# Main.net
KiCad netlist of a schematic drawn in EAGLE
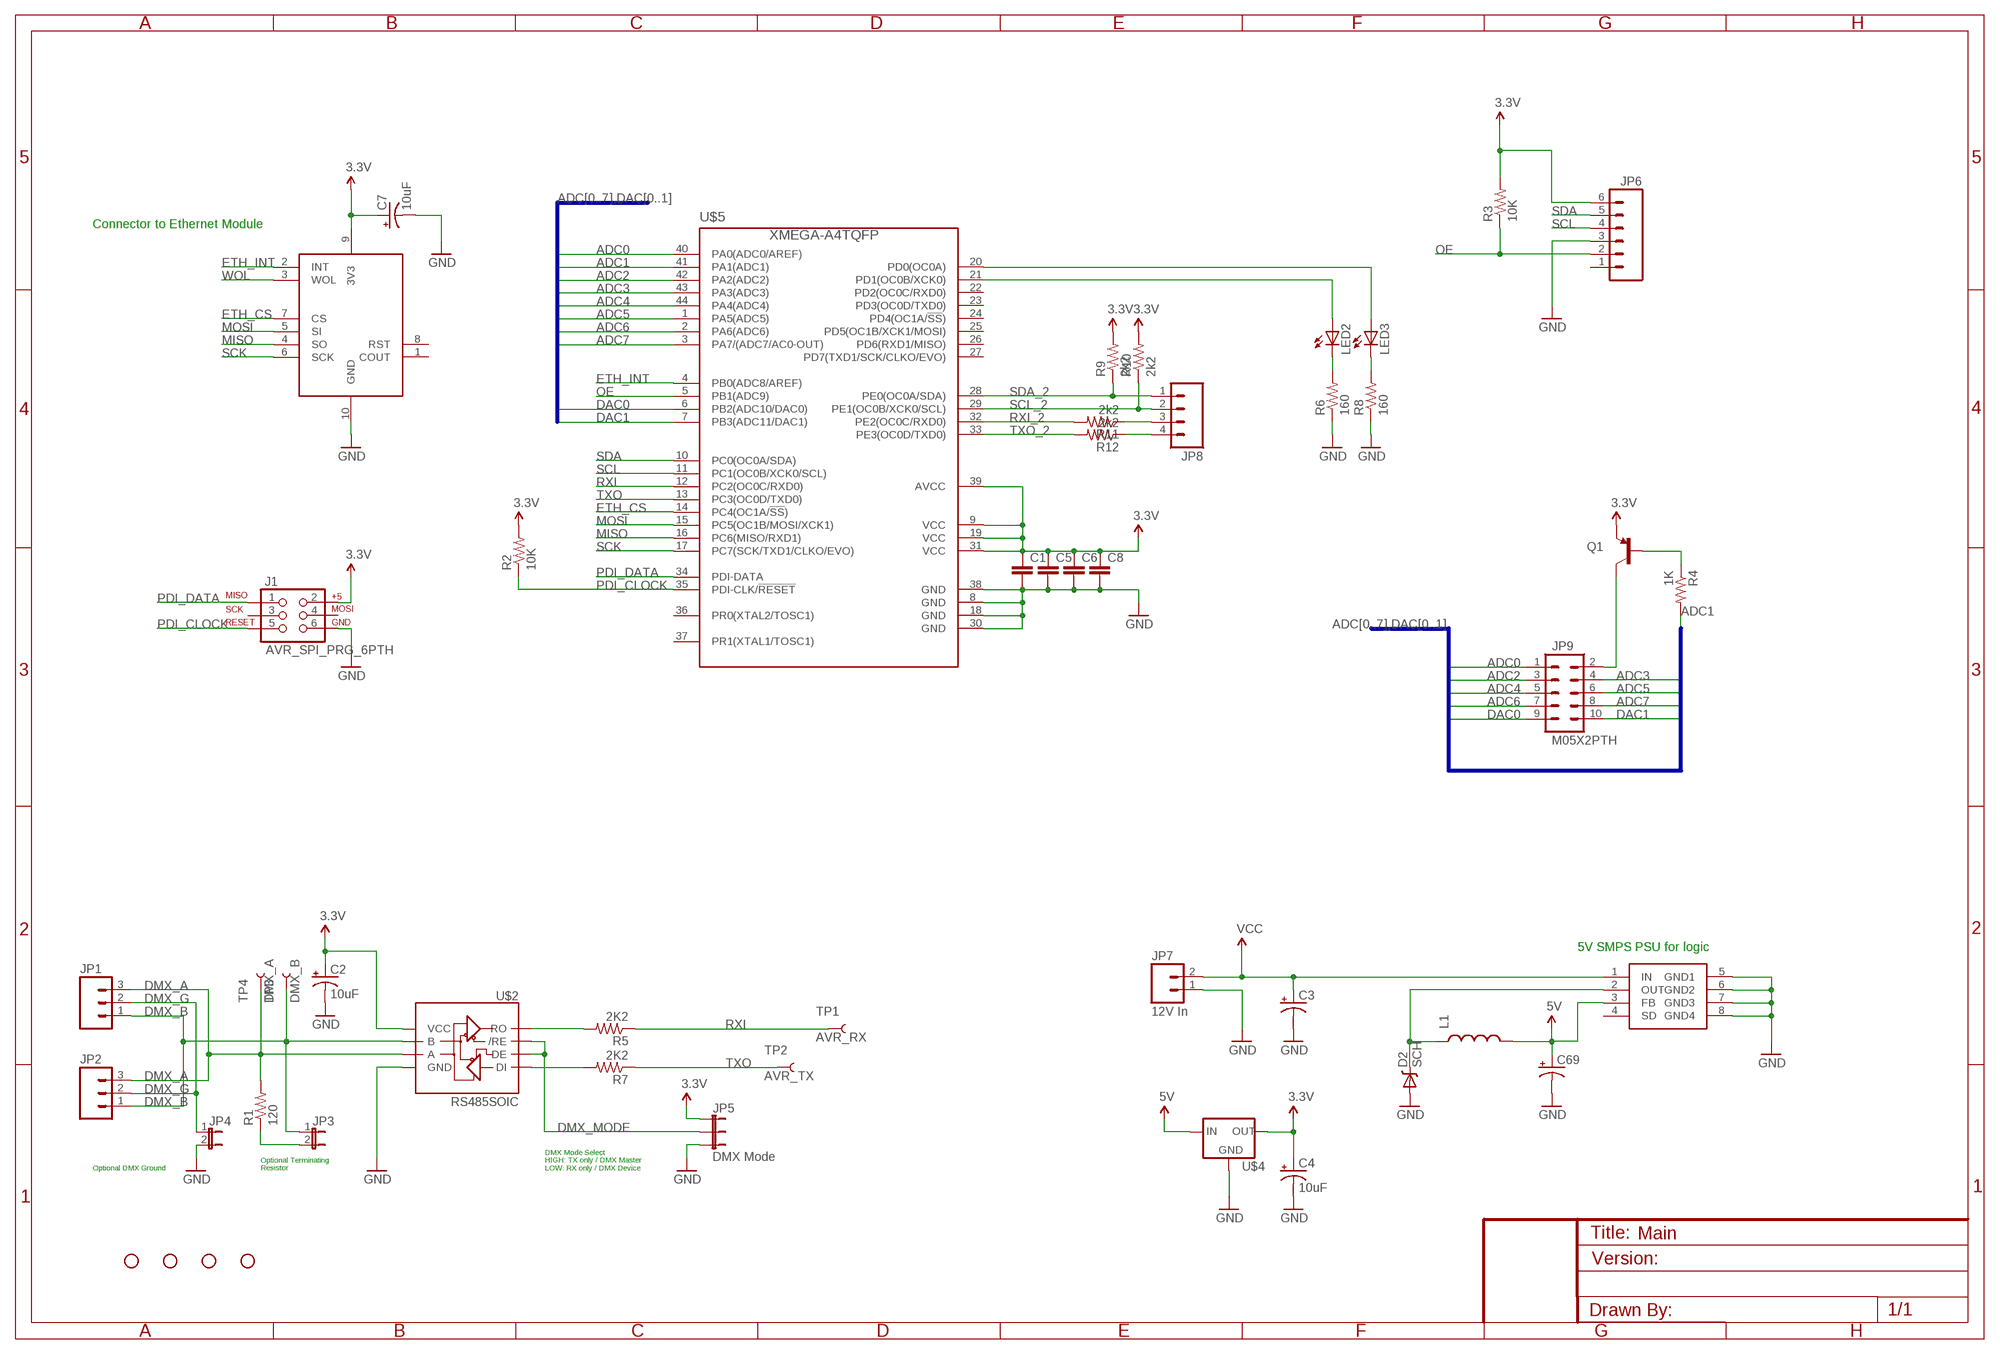
[diagram p0: schematic, sheet 1]

(export (version "E")
  (design (tool "Eeschema 10.0.6"))
  (components
    (comp (ref "C1")
      (value "CAP0603-CAP")
      (footprint "eagle-import:0603-CAP")
      (libsource (lib "eagle-import") (part "CAP0603-CAP"))
    )
    (comp (ref "C2")
      (value "10uF")
      (footprint "eagle-import:EIA3216")
      (libsource (lib "eagle-import") (part "CAP_POL1206"))
    )
    (comp (ref "C3")
      (value "CAP_POLPTH1")
      (footprint "eagle-import:CPOL-RADIAL-100UF-25V")
      (libsource (lib "eagle-import") (part "CAP_POLPTH1"))
    )
    (comp (ref "C4")
      (value "10uF")
      (footprint "eagle-import:EIA3216")
      (libsource (lib "eagle-import") (part "CAP_POL1206"))
    )
    (comp (ref "C5")
      (value "CAP0603-CAP")
      (footprint "eagle-import:0603-CAP")
      (libsource (lib "eagle-import") (part "CAP0603-CAP"))
    )
    (comp (ref "C6")
      (value "CAP0603-CAP")
      (footprint "eagle-import:0603-CAP")
      (libsource (lib "eagle-import") (part "CAP0603-CAP"))
    )
    (comp (ref "C7")
      (value "10uF")
      (footprint "eagle-import:EIA3216")
      (libsource (lib "eagle-import") (part "CAP_POL1206"))
    )
    (comp (ref "C8")
      (value "CAP0603-CAP")
      (footprint "eagle-import:0603-CAP")
      (libsource (lib "eagle-import") (part "CAP0603-CAP"))
    )
    (comp (ref "C69")
      (value "CAP_POLPTH1")
      (footprint "eagle-import:CPOL-RADIAL-100UF-25V")
      (libsource (lib "eagle-import") (part "CAP_POLPTH1"))
    )
    (comp (ref "D2")
      (value "SCH")
      (footprint "eagle-import:SMA-DIODE")
      (libsource (lib "eagle-import") (part "DIODE-SCHOTTKY_"))
    )
    (comp (ref "J1")
      (value "AVR_SPI_PRG_6PTH")
      (footprint "eagle-import:2X3")
      (libsource (lib "eagle-import") (part "AVR_SPI_PRG_6PTH"))
    )
    (comp (ref "JP1")
      (value "M03POLAR")
      (footprint "eagle-import:MOLEX-1X3")
      (libsource (lib "eagle-import") (part "M03POLAR"))
    )
    (comp (ref "JP2")
      (value "M03POLAR")
      (footprint "eagle-import:MOLEX-1X3")
      (libsource (lib "eagle-import") (part "M03POLAR"))
    )
    (comp (ref "JP3")
      (value "JUMPER-2PTH")
      (footprint "eagle-import:1X02")
      (libsource (lib "eagle-import") (part "JUMPER-2PTH"))
    )
    (comp (ref "JP4")
      (value "JUMPER-2PTH")
      (footprint "eagle-import:1X02")
      (libsource (lib "eagle-import") (part "JUMPER-2PTH"))
    )
    (comp (ref "JP5")
      (value "DMX Mode")
      (footprint "eagle-import:1X03")
      (libsource (lib "eagle-import") (part "JUMPER-3PTH"))
    )
    (comp (ref "JP6")
      (value "M06POLAR")
      (footprint "eagle-import:MOLEX-1X6")
      (libsource (lib "eagle-import") (part "M06POLAR"))
    )
    (comp (ref "JP7")
      (value "12V In")
      (footprint "eagle-import:SCREWTERMINAL-3.5MM-2")
      (libsource (lib "eagle-import") (part "M023.5MM"))
    )
    (comp (ref "JP8")
      (value "M04PTH")
      (footprint "eagle-import:1X04")
      (libsource (lib "eagle-import") (part "M04PTH"))
    )
    (comp (ref "JP9")
      (value "M05X2PTH")
      (footprint "eagle-import:AVR_ICSP")
      (libsource (lib "eagle-import") (part "M05X2PTH"))
    )
    (comp (ref "L1")
      (value "INDUCTOR1206H*")
      (footprint "eagle-import:INDUCTOR-1206")
      (libsource (lib "eagle-import") (part "INDUCTORH1206"))
    )
    (comp (ref "LED2")
      (value "LED5MM")
      (footprint "eagle-import:LED5MM")
      (libsource (lib "eagle-import") (part "LED5MM"))
    )
    (comp (ref "LED3")
      (value "LED5MM")
      (footprint "eagle-import:LED5MM")
      (libsource (lib "eagle-import") (part "LED5MM"))
    )
    (comp (ref "Q1")
      (value "TRANSISTOR_PNPSMD")
      (footprint "eagle-import:SOT23-3")
      (libsource (lib "eagle-import") (part "TRANSISTOR_PNPSMD"))
    )
    (comp (ref "R1")
      (value "120")
      (footprint "eagle-import:1206")
      (libsource (lib "eagle-import") (part "RESISTOR1206"))
    )
    (comp (ref "R2")
      (value "10K")
      (footprint "eagle-import:1206")
      (libsource (lib "eagle-import") (part "RESISTOR1206"))
    )
    (comp (ref "R3")
      (value "10K")
      (footprint "eagle-import:1206")
      (libsource (lib "eagle-import") (part "RESISTOR1206"))
    )
    (comp (ref "R4")
      (value "1K")
      (footprint "eagle-import:1206")
      (libsource (lib "eagle-import") (part "RESISTOR1206"))
    )
    (comp (ref "R5")
      (value "2K2")
      (footprint "eagle-import:1206")
      (libsource (lib "eagle-import") (part "RESISTOR1206"))
    )
    (comp (ref "R6")
      (value "160")
      (footprint "eagle-import:1206")
      (libsource (lib "eagle-import") (part "RESISTOR1206"))
    )
    (comp (ref "R7")
      (value "2K2")
      (footprint "eagle-import:1206")
      (libsource (lib "eagle-import") (part "RESISTOR1206"))
    )
    (comp (ref "R8")
      (value "160")
      (footprint "eagle-import:1206")
      (libsource (lib "eagle-import") (part "RESISTOR1206"))
    )
    (comp (ref "R9")
      (value "2k2")
      (footprint "eagle-import:1206")
      (libsource (lib "eagle-import") (part "RESISTOR1206"))
    )
    (comp (ref "R10")
      (value "2k2")
      (footprint "eagle-import:1206")
      (libsource (lib "eagle-import") (part "RESISTOR1206"))
    )
    (comp (ref "R11")
      (value "2k2")
      (footprint "eagle-import:1206")
      (libsource (lib "eagle-import") (part "RESISTOR1206"))
    )
    (comp (ref "R12")
      (value "2k2")
      (footprint "eagle-import:1206")
      (libsource (lib "eagle-import") (part "RESISTOR1206"))
    )
    (comp (ref "STANDOFF1")
      (value "STAND-OFF")
      (footprint "eagle-import:STAND-OFF")
      (libsource (lib "eagle-import") (part "STAND-OFF"))
    )
    (comp (ref "STANDOFF2")
      (value "STAND-OFF")
      (footprint "eagle-import:STAND-OFF")
      (libsource (lib "eagle-import") (part "STAND-OFF"))
    )
    (comp (ref "STANDOFF3")
      (value "STAND-OFF")
      (footprint "eagle-import:STAND-OFF")
      (libsource (lib "eagle-import") (part "STAND-OFF"))
    )
    (comp (ref "STANDOFF4")
      (value "STAND-OFF")
      (footprint "eagle-import:STAND-OFF")
      (libsource (lib "eagle-import") (part "STAND-OFF"))
    )
    (comp (ref "TP1")
      (value "AVR_RX")
      (footprint "eagle-import:PAD.03X.05")
      (libsource (lib "eagle-import") (part "TEST-POINT3X5"))
    )
    (comp (ref "TP2")
      (value "AVR_TX")
      (footprint "eagle-import:PAD.03X.05")
      (libsource (lib "eagle-import") (part "TEST-POINT3X5"))
    )
    (comp (ref "TP3")
      (value "DMX_B")
      (footprint "eagle-import:PAD.03X.05")
      (libsource (lib "eagle-import") (part "TEST-POINT3X5"))
    )
    (comp (ref "TP4")
      (value "DMX_A")
      (footprint "eagle-import:PAD.03X.05")
      (libsource (lib "eagle-import") (part "TEST-POINT3X5"))
    )
    (comp (ref "U$1")
      (value "ETHMODULE")
      (footprint "eagle-import:2X5")
      (libsource (lib "eagle-import") (part "ETHMODULE"))
    )
    (comp (ref "U$2")
      (value "RS485SOIC")
      (footprint "eagle-import:SO08")
      (libsource (lib "eagle-import") (part "RS485SOIC"))
    )
    (comp (ref "U$3")
      (value "AP1509-33")
      (footprint "eagle-import:SOIC-8")
      (libsource (lib "eagle-import") (part "AP1509-33"))
    )
    (comp (ref "U$4")
      (value "V_REG_MIC2920")
      (footprint "eagle-import:SOT223")
      (libsource (lib "eagle-import") (part "V_REG_MIC2920"))
    )
    (comp (ref "U$5")
      (value "XMEGA-A4TQFP")
      (footprint "eagle-import:TQFP44")
      (libsource (lib "eagle-import") (part "XMEGA-A4TQFP"))
    )
  )
  (nets
    (net (code "1") (name "/ADC0") (class "Default")
      (node (ref "JP9") (pin "1") (pinfunction "1_1") (pintype "passive"))
      (node (ref "U$5") (pin "40") (pinfunction "PA0(ADC0/AREF)_40") (pintype "bidirectional"))
    )
    (net (code "2") (name "/ADC1") (class "Default")
      (node (ref "R4") (pin "2") (pinfunction "2_2") (pintype "passive"))
      (node (ref "U$5") (pin "41") (pinfunction "PA1(ADC1)_41") (pintype "bidirectional"))
    )
    (net (code "3") (name "/ADC2") (class "Default")
      (node (ref "JP9") (pin "3") (pinfunction "3_3") (pintype "passive"))
      (node (ref "U$5") (pin "42") (pinfunction "PA2(ADC2)_42") (pintype "bidirectional"))
    )
    (net (code "4") (name "/ADC3") (class "Default")
      (node (ref "JP9") (pin "4") (pinfunction "4_4") (pintype "passive"))
      (node (ref "U$5") (pin "43") (pinfunction "PA3(ADC3)_43") (pintype "bidirectional"))
    )
    (net (code "5") (name "/ADC4") (class "Default")
      (node (ref "JP9") (pin "5") (pinfunction "5_5") (pintype "passive"))
      (node (ref "U$5") (pin "44") (pinfunction "PA4(ADC4)_44") (pintype "bidirectional"))
    )
    (net (code "6") (name "/ADC5") (class "Default")
      (node (ref "JP9") (pin "6") (pinfunction "6_6") (pintype "passive"))
      (node (ref "U$5") (pin "1") (pinfunction "PA5(ADC5)_1") (pintype "bidirectional"))
    )
    (net (code "7") (name "/ADC6") (class "Default")
      (node (ref "JP9") (pin "7") (pinfunction "7_7") (pintype "passive"))
      (node (ref "U$5") (pin "2") (pinfunction "PA6(ADC6)_2") (pintype "bidirectional"))
    )
    (net (code "8") (name "/ADC7") (class "Default")
      (node (ref "JP9") (pin "8") (pinfunction "8_8") (pintype "passive"))
      (node (ref "U$5") (pin "3") (pinfunction "PA7/(ADC7/AC0-OUT)_3") (pintype "bidirectional"))
    )
    (net (code "9") (name "/COUT") (class "Default")
      (node (ref "U$1") (pin "1") (pinfunction "COUT_1") (pintype "power_in"))
    )
    (net (code "10") (name "/DAC0") (class "Default")
      (node (ref "JP9") (pin "9") (pinfunction "9_9") (pintype "passive"))
      (node (ref "U$5") (pin "6") (pinfunction "PB2(ADC10/DAC0)_6") (pintype "bidirectional"))
    )
    (net (code "11") (name "/DAC1") (class "Default")
      (node (ref "JP9") (pin "10") (pinfunction "10_10") (pintype "passive"))
      (node (ref "U$5") (pin "7") (pinfunction "PB3(ADC11/DAC1)_7") (pintype "bidirectional"))
    )
    (net (code "12") (name "/DMX_A") (class "Default")
      (node (ref "JP1") (pin "3") (pinfunction "3_3") (pintype "passive"))
      (node (ref "JP2") (pin "3") (pinfunction "3_3") (pintype "passive"))
      (node (ref "R1") (pin "2") (pinfunction "2_2") (pintype "passive"))
      (node (ref "TP4") (pin "P$1") (pinfunction "1_P$1") (pintype "bidirectional"))
      (node (ref "U$2") (pin "6") (pinfunction "A_6") (pintype "bidirectional"))
    )
    (net (code "13") (name "/DMX_B") (class "Default")
      (node (ref "JP1") (pin "1") (pinfunction "1_1") (pintype "passive"))
      (node (ref "JP2") (pin "1") (pinfunction "1_1") (pintype "passive"))
      (node (ref "JP3") (pin "1") (pinfunction "1_1") (pintype "passive"))
      (node (ref "TP3") (pin "P$1") (pinfunction "1_P$1") (pintype "bidirectional"))
      (node (ref "U$2") (pin "7") (pinfunction "B_7") (pintype "bidirectional"))
    )
    (net (code "14") (name "/DMX_G") (class "Default")
      (node (ref "JP1") (pin "2") (pinfunction "2_2") (pintype "passive"))
      (node (ref "JP2") (pin "2") (pinfunction "2_2") (pintype "passive"))
      (node (ref "JP4") (pin "1") (pinfunction "1_1") (pintype "passive"))
    )
    (net (code "15") (name "/DMX_MODE") (class "Default")
      (node (ref "JP5") (pin "2") (pinfunction "2_2") (pintype "passive"))
      (node (ref "U$2") (pin "2") (pinfunction "/RE_2") (pintype "bidirectional"))
      (node (ref "U$2") (pin "3") (pinfunction "DE_3") (pintype "bidirectional"))
    )
    (net (code "16") (name "/ETH_CS") (class "Default")
      (node (ref "U$1") (pin "7") (pinfunction "CS_7") (pintype "power_in"))
      (node (ref "U$5") (pin "14") (pinfunction "PC4(OC1A/~{SS})_14") (pintype "bidirectional"))
    )
    (net (code "17") (name "/ETH_INT") (class "Default")
      (node (ref "U$1") (pin "2") (pinfunction "INT_2") (pintype "power_in"))
      (node (ref "U$5") (pin "4") (pinfunction "PB0(ADC8/AREF)_4") (pintype "bidirectional"))
    )
    (net (code "18") (name "/MISO") (class "Default")
      (node (ref "U$1") (pin "4") (pinfunction "SO_4") (pintype "power_in"))
      (node (ref "U$5") (pin "16") (pinfunction "PC6(MISO/RXD1)_16") (pintype "bidirectional"))
    )
    (net (code "19") (name "/MOSI") (class "Default")
      (node (ref "U$1") (pin "5") (pinfunction "SI_5") (pintype "power_in"))
      (node (ref "U$5") (pin "15") (pinfunction "PC5(OC1B/MOSI/XCK1)_15") (pintype "bidirectional"))
    )
    (net (code "20") (name "/OE") (class "Default")
      (node (ref "JP6") (pin "2") (pinfunction "2_2") (pintype "passive"))
      (node (ref "R3") (pin "1") (pinfunction "1_1") (pintype "passive"))
      (node (ref "U$5") (pin "5") (pinfunction "PB1(ADC9)_5") (pintype "bidirectional"))
    )
    (net (code "21") (name "/PDI_CLOCK") (class "Default")
      (node (ref "J1") (pin "5") (pinfunction "5_5") (pintype "passive"))
      (node (ref "R2") (pin "1") (pinfunction "1_1") (pintype "passive"))
      (node (ref "U$5") (pin "35") (pinfunction "PDI-CLK/~{RESET}_35") (pintype "input"))
    )
    (net (code "22") (name "/PDI_DATA") (class "Default")
      (node (ref "J1") (pin "1") (pinfunction "1_1") (pintype "passive"))
      (node (ref "U$5") (pin "34") (pinfunction "PDI-DATA_34") (pintype "bidirectional"))
    )
    (net (code "23") (name "/RST") (class "Default")
      (node (ref "U$1") (pin "8") (pinfunction "RST_8") (pintype "power_in"))
    )
    (net (code "24") (name "/RXI") (class "Default")
      (node (ref "R5") (pin "1") (pinfunction "1_1") (pintype "passive"))
      (node (ref "TP1") (pin "P$1") (pinfunction "1_P$1") (pintype "bidirectional"))
      (node (ref "U$5") (pin "12") (pinfunction "PC2(OC0C/RXD0)_12") (pintype "bidirectional"))
    )
    (net (code "25") (name "/RXI_2") (class "Default")
      (node (ref "R11") (pin "2") (pinfunction "2_2") (pintype "passive"))
      (node (ref "U$5") (pin "32") (pinfunction "PE2(OC0C/RXD0)_32") (pintype "bidirectional"))
    )
    (net (code "26") (name "/SCK") (class "Default")
      (node (ref "U$1") (pin "6") (pinfunction "SCK_6") (pintype "power_in"))
      (node (ref "U$5") (pin "17") (pinfunction "PC7(SCK/TXD1/CLKO/EVO)_17") (pintype "bidirectional"))
    )
    (net (code "27") (name "/SCL") (class "Default")
      (node (ref "JP6") (pin "4") (pinfunction "4_4") (pintype "passive"))
      (node (ref "U$5") (pin "11") (pinfunction "PC1(OC0B/XCK0/SCL)_11") (pintype "bidirectional"))
    )
    (net (code "28") (name "/SCL_2") (class "Default")
      (node (ref "JP8") (pin "2") (pinfunction "2_2") (pintype "passive"))
      (node (ref "R10") (pin "1") (pinfunction "1_1") (pintype "passive"))
      (node (ref "U$5") (pin "29") (pinfunction "PE1(OC0B/XCK0/SCL)_29") (pintype "bidirectional"))
    )
    (net (code "29") (name "/SDA") (class "Default")
      (node (ref "JP6") (pin "5") (pinfunction "5_5") (pintype "passive"))
      (node (ref "U$5") (pin "10") (pinfunction "PC0(OC0A/SDA)_10") (pintype "bidirectional"))
    )
    (net (code "30") (name "/SDA_2") (class "Default")
      (node (ref "JP8") (pin "1") (pinfunction "1_1") (pintype "passive"))
      (node (ref "R9") (pin "1") (pinfunction "1_1") (pintype "passive"))
      (node (ref "U$5") (pin "28") (pinfunction "PE0(OC0A/SDA)_28") (pintype "bidirectional"))
    )
    (net (code "31") (name "/TXO") (class "Default")
      (node (ref "R7") (pin "1") (pinfunction "1_1") (pintype "passive"))
      (node (ref "TP2") (pin "P$1") (pinfunction "1_P$1") (pintype "bidirectional"))
      (node (ref "U$5") (pin "13") (pinfunction "PC3(OC0D/TXD0)_13") (pintype "bidirectional"))
    )
    (net (code "32") (name "/TXO_2") (class "Default")
      (node (ref "R12") (pin "2") (pinfunction "2_2") (pintype "passive"))
      (node (ref "U$5") (pin "33") (pinfunction "PE3(OC0D/TXD0)_33") (pintype "bidirectional"))
    )
    (net (code "33") (name "/WOL") (class "Default")
      (node (ref "U$1") (pin "3") (pinfunction "WOL_3") (pintype "power_in"))
    )
    (net (code "35") (name "3.3V") (class "Default")
      (node (ref "C1") (pin "1") (pinfunction "1_1") (pintype "passive"))
      (node (ref "C2") (pin "A") (pinfunction "+_A") (pintype "passive"))
      (node (ref "C4") (pin "A") (pinfunction "+_A") (pintype "passive"))
      (node (ref "C5") (pin "1") (pinfunction "1_1") (pintype "passive"))
      (node (ref "C6") (pin "1") (pinfunction "1_1") (pintype "passive"))
      (node (ref "C7") (pin "A") (pinfunction "+_A") (pintype "passive"))
      (node (ref "C8") (pin "1") (pinfunction "1_1") (pintype "passive"))
      (node (ref "J1") (pin "2") (pinfunction "2_2") (pintype "passive"))
      (node (ref "JP5") (pin "1") (pinfunction "1_1") (pintype "passive"))
      (node (ref "JP6") (pin "6") (pinfunction "6_6") (pintype "passive"))
      (node (ref "Q1") (pin "2") (pinfunction "E_2") (pintype "passive"))
      (node (ref "R10") (pin "2") (pinfunction "2_2") (pintype "passive"))
      (node (ref "R2") (pin "2") (pinfunction "2_2") (pintype "passive"))
      (node (ref "R3") (pin "2") (pinfunction "2_2") (pintype "passive"))
      (node (ref "R9") (pin "2") (pinfunction "2_2") (pintype "passive"))
      (node (ref "U$1") (pin "9") (pinfunction "3V3_9") (pintype "power_in"))
      (node (ref "U$2") (pin "8") (pinfunction "VCC_8") (pintype "bidirectional"))
      (node (ref "U$4") (pin "3") (pinfunction "OUT_3") (pintype "output"))
      (node (ref "U$5") (pin "19") (pinfunction "VCC_19") (pintype "power_in"))
      (node (ref "U$5") (pin "31") (pinfunction "VCC_31") (pintype "power_in"))
      (node (ref "U$5") (pin "39") (pinfunction "AVCC_39") (pintype "power_in"))
      (node (ref "U$5") (pin "9") (pinfunction "VCC_9") (pintype "power_in"))
    )
    (net (code "36") (name "5V") (class "Default")
      (node (ref "C69") (pin "1") (pinfunction "+_1") (pintype "passive"))
      (node (ref "L1") (pin "P$2") (pinfunction "2_P$2") (pintype "passive"))
      (node (ref "U$3") (pin "3") (pinfunction "FB_3") (pintype "bidirectional"))
      (node (ref "U$4") (pin "1") (pinfunction "IN_1") (pintype "input"))
    )
    (net (code "37") (name "GND") (class "Default")
      (node (ref "C1") (pin "2") (pinfunction "2_2") (pintype "passive"))
      (node (ref "C2") (pin "C") (pinfunction "-_C") (pintype "passive"))
      (node (ref "C3") (pin "2") (pinfunction "-_2") (pintype "passive"))
      (node (ref "C4") (pin "C") (pinfunction "-_C") (pintype "passive"))
      (node (ref "C5") (pin "2") (pinfunction "2_2") (pintype "passive"))
      (node (ref "C6") (pin "2") (pinfunction "2_2") (pintype "passive"))
      (node (ref "C69") (pin "2") (pinfunction "-_2") (pintype "passive"))
      (node (ref "C7") (pin "C") (pinfunction "-_C") (pintype "passive"))
      (node (ref "C8") (pin "2") (pinfunction "2_2") (pintype "passive"))
      (node (ref "D2") (pin "A") (pinfunction "A_A") (pintype "passive"))
      (node (ref "J1") (pin "6") (pinfunction "6_6") (pintype "passive"))
      (node (ref "JP4") (pin "2") (pinfunction "2_2") (pintype "passive"))
      (node (ref "JP5") (pin "3") (pinfunction "3_3") (pintype "passive"))
      (node (ref "JP6") (pin "3") (pinfunction "3_3") (pintype "passive"))
      (node (ref "JP7") (pin "1") (pinfunction "1_1") (pintype "passive"))
      (node (ref "R6") (pin "1") (pinfunction "1_1") (pintype "passive"))
      (node (ref "R8") (pin "1") (pinfunction "1_1") (pintype "passive"))
      (node (ref "U$1") (pin "10") (pinfunction "GND_10") (pintype "power_in"))
      (node (ref "U$2") (pin "5") (pinfunction "GND_5") (pintype "bidirectional"))
      (node (ref "U$3") (pin "5") (pinfunction "GND1_5") (pintype "bidirectional"))
      (node (ref "U$3") (pin "6") (pinfunction "GND2_6") (pintype "bidirectional"))
      (node (ref "U$3") (pin "7") (pinfunction "GND3_7") (pintype "bidirectional"))
      (node (ref "U$3") (pin "8") (pinfunction "GND4_8") (pintype "bidirectional"))
      (node (ref "U$4") (pin "2") (pinfunction "GND_2") (pintype "input"))
      (node (ref "U$5") (pin "18") (pinfunction "GND_18") (pintype "power_in"))
      (node (ref "U$5") (pin "30") (pinfunction "GND_30") (pintype "power_in"))
      (node (ref "U$5") (pin "38") (pinfunction "GND_38") (pintype "power_in"))
      (node (ref "U$5") (pin "8") (pinfunction "GND_8") (pintype "power_in"))
    )
    (net (code "38") (name "Net-(JP3-Pad2)") (class "Default")
      (node (ref "JP3") (pin "2") (pinfunction "2_2") (pintype "passive"))
      (node (ref "R1") (pin "1") (pinfunction "1_1") (pintype "passive"))
    )
    (net (code "39") (name "Net-(JP8-Pad3)") (class "Default")
      (node (ref "JP8") (pin "3") (pinfunction "3_3") (pintype "passive"))
      (node (ref "R11") (pin "1") (pinfunction "1_1") (pintype "passive"))
    )
    (net (code "40") (name "Net-(JP8-Pad4)") (class "Default")
      (node (ref "JP8") (pin "4") (pinfunction "4_4") (pintype "passive"))
      (node (ref "R12") (pin "1") (pinfunction "1_1") (pintype "passive"))
    )
    (net (code "41") (name "Net-(L1-1)") (class "Default")
      (node (ref "D2") (pin "C") (pinfunction "C_C") (pintype "passive"))
      (node (ref "L1") (pin "P$1") (pinfunction "1_P$1") (pintype "passive"))
      (node (ref "U$3") (pin "2") (pinfunction "OUT_2") (pintype "bidirectional"))
    )
    (net (code "42") (name "Net-(LED2-C)") (class "Default")
      (node (ref "LED2") (pin "K") (pinfunction "C_K") (pintype "passive"))
      (node (ref "R6") (pin "2") (pinfunction "2_2") (pintype "passive"))
    )
    (net (code "43") (name "Net-(LED3-C)") (class "Default")
      (node (ref "LED3") (pin "K") (pinfunction "C_K") (pintype "passive"))
      (node (ref "R8") (pin "2") (pinfunction "2_2") (pintype "passive"))
    )
    (net (code "44") (name "Net-(Q1-B)") (class "Default")
      (node (ref "Q1") (pin "1") (pinfunction "B_1") (pintype "passive"))
      (node (ref "R4") (pin "1") (pinfunction "1_1") (pintype "passive"))
    )
    (net (code "45") (name "Net-(Q1-C)") (class "Default")
      (node (ref "JP9") (pin "2") (pinfunction "2_2") (pintype "passive"))
      (node (ref "Q1") (pin "3") (pinfunction "C_3") (pintype "passive"))
    )
    (net (code "46") (name "Net-(U$2-DI)") (class "Default")
      (node (ref "R7") (pin "2") (pinfunction "2_2") (pintype "passive"))
      (node (ref "U$2") (pin "4") (pinfunction "DI_4") (pintype "bidirectional"))
    )
    (net (code "47") (name "Net-(U$2-RO)") (class "Default")
      (node (ref "R5") (pin "2") (pinfunction "2_2") (pintype "passive"))
      (node (ref "U$2") (pin "1") (pinfunction "RO_1") (pintype "bidirectional"))
    )
    (net (code "48") (name "Net-(U$5-PD0(OC0A))") (class "Default")
      (node (ref "LED3") (pin "A") (pinfunction "A_A") (pintype "passive"))
      (node (ref "U$5") (pin "20") (pinfunction "PD0(OC0A)_20") (pintype "bidirectional"))
    )
    (net (code "49") (name "Net-(U$5-PD1(OC0B{slash}XCK0))") (class "Default")
      (node (ref "LED2") (pin "A") (pinfunction "A_A") (pintype "passive"))
      (node (ref "U$5") (pin "21") (pinfunction "PD1(OC0B/XCK0)_21") (pintype "bidirectional"))
    )
    (net (code "50") (name "VCC") (class "Default")
      (node (ref "C3") (pin "1") (pinfunction "+_1") (pintype "passive"))
      (node (ref "JP7") (pin "2") (pinfunction "2_2") (pintype "passive"))
      (node (ref "U$3") (pin "1") (pinfunction "IN_1") (pintype "bidirectional"))
    )
    (net (code "51") (name "unconnected-(J1-Pad3)") (class "Default")
      (node (ref "J1") (pin "3") (pinfunction "3_3") (pintype "passive"))
    )
    (net (code "52") (name "unconnected-(J1-Pad4)") (class "Default")
      (node (ref "J1") (pin "4") (pinfunction "4_4") (pintype "passive"))
    )
    (net (code "53") (name "unconnected-(JP6-Pad1)") (class "Default")
      (node (ref "JP6") (pin "1") (pinfunction "1_1") (pintype "passive"))
    )
    (net (code "54") (name "unconnected-(U$3-SD-Pad4)") (class "Default")
      (node (ref "U$3") (pin "4") (pinfunction "SD_4") (pintype "bidirectional"))
    )
    (net (code "55") (name "unconnected-(U$5-PD2(OC0C{slash}RXD0)-Pad22)") (class "Default")
      (node (ref "U$5") (pin "22") (pinfunction "PD2(OC0C/RXD0)_22") (pintype "bidirectional"))
    )
    (net (code "56") (name "unconnected-(U$5-PD3(OC0D{slash}TXD0)-Pad23)") (class "Default")
      (node (ref "U$5") (pin "23") (pinfunction "PD3(OC0D/TXD0)_23") (pintype "bidirectional"))
    )
    (net (code "57") (name "unconnected-(U$5-PD4(OC1A{slash}~{SS})-Pad24)") (class "Default")
      (node (ref "U$5") (pin "24") (pinfunction "PD4(OC1A/~{SS})_24") (pintype "bidirectional"))
    )
    (net (code "58") (name "unconnected-(U$5-PD5(OC1B{slash}XCK1{slash}MOSI)-Pad25)") (class "Default")
      (node (ref "U$5") (pin "25") (pinfunction "PD5(OC1B/XCK1/MOSI)_25") (pintype "bidirectional"))
    )
    (net (code "59") (name "unconnected-(U$5-PD6(RXD1{slash}MISO)-Pad26)") (class "Default")
      (node (ref "U$5") (pin "26") (pinfunction "PD6(RXD1/MISO)_26") (pintype "bidirectional"))
    )
    (net (code "60") (name "unconnected-(U$5-PD7(TXD1{slash}SCK{slash}CLKO{slash}EVO)-Pad27)") (class "Default")
      (node (ref "U$5") (pin "27") (pinfunction "PD7(TXD1/SCK/CLKO/EVO)_27") (pintype "bidirectional"))
    )
    (net (code "61") (name "unconnected-(U$5-PR0(XTAL2{slash}TOSC1)-Pad36)") (class "Default")
      (node (ref "U$5") (pin "36") (pinfunction "PR0(XTAL2/TOSC1)_36") (pintype "bidirectional"))
    )
    (net (code "62") (name "unconnected-(U$5-PR1(XTAL1{slash}TOSC1)-Pad37)") (class "Default")
      (node (ref "U$5") (pin "37") (pinfunction "PR1(XTAL1/TOSC1)_37") (pintype "bidirectional"))
    )
  )
)
